# Power.net
KiCad netlist of a schematic drawn in Altium Designer
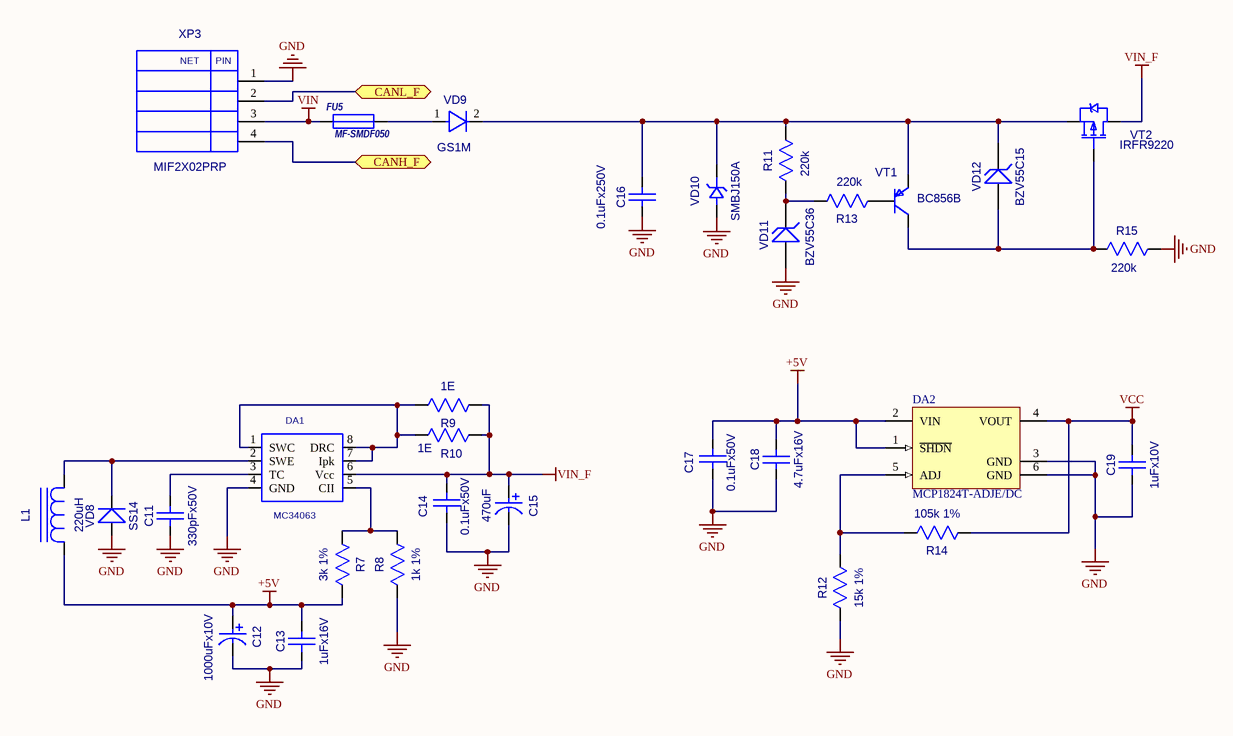
[diagram p0: Power.SchDoc]

(export (version "E")
  (design (tool "Eeschema 10.0.6"))
  (components
    (comp (ref "C11")
      (value "330pFx50V")
      (footprint "CC0603-3M")
      (description "CC0603")
      (libsource (lib "gprs_modem") (part "CC0603"))
    )
    (comp (ref "C12")
      (value "1000uFx10V")
      (footprint "CC8X3.5")
      (description "CAP0.35")
      (libsource (lib "gprs_modem") (part "CAP0.35"))
    )
    (comp (ref "C13")
      (value "1uFx16V")
      (footprint "CC0603-3M")
      (description "CC0603")
      (libsource (lib "gprs_modem") (part "CC0603"))
    )
    (comp (ref "C14")
      (value "0.1uFx50V")
      (footprint "CC0603-3M")
      (description "CC0603")
      (libsource (lib "gprs_modem") (part "CC0603"))
    )
    (comp (ref "C15")
      (value "470uF")
      (footprint "CC16X10_CAP0.5(1)(Primary)")
      (description "CAP0.5(1)")
      (libsource (lib "gprs_modem") (part "CAP0.5(1)"))
    )
    (comp (ref "C16")
      (value "0.1uFx250V")
      (footprint "CC1206-MIDI")
      (description "CC1206")
      (libsource (lib "gprs_modem") (part "CC1206"))
    )
    (comp (ref "C17")
      (value "0.1uFx50V")
      (footprint "CC0603-3M")
      (description "CC0603")
      (libsource (lib "gprs_modem") (part "CC0603"))
    )
    (comp (ref "C18")
      (value "4.7uFx16V")
      (footprint "CC0805-MIDI-2M1")
      (description "CC0805")
      (libsource (lib "gprs_modem") (part "CC0805"))
    )
    (comp (ref "C19")
      (value "1uFx10V")
      (footprint "CC0603-3M")
      (description "CC0603")
      (libsource (lib "gprs_modem") (part "CC0603"))
    )
    (comp (ref "DA1") (value "MC34063") (footprint "SO-8") (libsource (lib "Schetchik") (part "MC34063")))
    (comp (ref "DA2")
      (value "MCP1824T-ADJE/DC")
      (footprint "SOT223-6")
      (fields (field (name "PUBLISHER") "Altium Limited"))
      (libsource (lib "gprs_modem") (part "MCP1824T-ADJE/DC"))
    )
    (comp (ref "FU5")
      (value "MF-SMDF050")
      (footprint "MF-SMDF")
      (description "MF-SMDF")
      (libsource (lib "gprs_modem") (part "MF-SMDF"))
    )
    (comp (ref "L1")
      (value "220uH")
      (footprint "SDR0805")
      (description "SDR0805")
      (libsource (lib "gprs_modem") (part "SDR0805"))
    )
    (comp (ref "R7")
      (value "3k 1%")
      (footprint "RC0603-3M")
      (description "RC0603")
      (libsource (lib "gprs_modem") (part "RC0603"))
    )
    (comp (ref "R8")
      (value "1k 1%")
      (footprint "RC0603-3M")
      (description "RC0603")
      (libsource (lib "gprs_modem") (part "RC0603"))
    )
    (comp (ref "R9")
      (value "1E")
      (footprint "RC0805_IPC_NOM")
      (description "RC0805")
      (libsource (lib "gprs_modem") (part "RC0805"))
    )
    (comp (ref "R10")
      (value "1E")
      (footprint "RC0805_IPC_NOM")
      (description "RC0805")
      (libsource (lib "gprs_modem") (part "RC0805"))
    )
    (comp (ref "R11")
      (value "220k")
      (footprint "RC1206-2M")
      (description "RC1206")
      (libsource (lib "gprs_modem") (part "RC1206"))
    )
    (comp (ref "R12")
      (value "15k 1%")
      (footprint "RC0603-3M")
      (description "RC0603")
      (libsource (lib "gprs_modem") (part "RC0603"))
    )
    (comp (ref "R13")
      (value "220k")
      (footprint "RC1206-2M")
      (description "RC1206")
      (libsource (lib "gprs_modem") (part "RC1206"))
    )
    (comp (ref "R14")
      (value "105k 1%")
      (footprint "RC0603-3M")
      (description "RC0603")
      (libsource (lib "gprs_modem") (part "RC0603"))
    )
    (comp (ref "R15")
      (value "220k")
      (footprint "RC1206-2M")
      (description "RC1206")
      (libsource (lib "gprs_modem") (part "RC1206"))
    )
    (comp (ref "VD8")
      (value "SS14")
      (footprint "SMA")
      (description "Schottky Rectifier")
      (libsource (lib "gprs_modem") (part "SS14"))
    )
    (comp (ref "VD9") (value "GS1M") (footprint "SMA") (libsource (lib "Schetchik") (part "GS1M")))
    (comp (ref "VD10")
      (value "SMBJ150A")
      (footprint "SMB")
      (description "SMBJ")
      (libsource (lib "gprs_modem") (part "SMBJ"))
    )
    (comp (ref "VD11")
      (value "BZV55C36")
      (footprint "SOD-80")
      (description "Zener Voltage Regulator Diode")
      (libsource (lib "gprs_modem") (part "BZV55C12"))
    )
    (comp (ref "VD12")
      (value "BZV55C15")
      (footprint "SOD-80")
      (description "Zener Voltage Regulator Diode")
      (libsource (lib "gprs_modem") (part "BZV55C12"))
    )
    (comp (ref "VT1")
      (value "BC856B")
      (footprint "SOT-23(123)")
      (libsource (lib "Schetchik") (part "BC856B"))
    )
    (comp (ref "VT2")
      (value "IRFR9220")
      (footprint "D-PAK(TO-252AA)")
      (description "HEXFET Power MOSFET")
      (libsource (lib "gprs_modem") (part "IRFR9220"))
    )
    (comp (ref "XP3")
      (value "MIF2X02PRP")
      (footprint "MIF2X02PRP")
      (libsource (lib "Schetchik") (part "MIF2X02PRP"))
    )
  )
  (nets
    (net (code "1") (name "+5V") (class "Default")
      (node (ref "C12") (pin "1") (pintype "passive"))
      (node (ref "C13") (pin "2") (pinfunction "B_2") (pintype "passive"))
      (node (ref "C17") (pin "1") (pinfunction "A_1") (pintype "passive"))
      (node (ref "C18") (pin "2") (pinfunction "B_2") (pintype "passive"))
      (node (ref "DA2") (pin "1") (pinfunction "~{SHDN}_1") (pintype "input"))
      (node (ref "DA2") (pin "2") (pinfunction "VIN_2") (pintype "power_in"))
      (node (ref "L1") (pin "1") (pinfunction "C_1") (pintype "passive"))
      (node (ref "R7") (pin "2") (pinfunction "B_2") (pintype "passive"))
    )
    (net (code "2") (name "/CANH_F") (class "Default")
      (node (ref "XP3") (pin "4") (pinfunction "4_4") (pintype "passive"))
    )
    (net (code "3") (name "/CANL_F") (class "Default")
      (node (ref "XP3") (pin "2") (pinfunction "2_2") (pintype "passive"))
    )
    (net (code "4") (name "GND") (class "Default")
      (node (ref "C11") (pin "1") (pinfunction "A_1") (pintype "passive"))
      (node (ref "C12") (pin "2") (pintype "passive"))
      (node (ref "C13") (pin "1") (pinfunction "A_1") (pintype "passive"))
      (node (ref "C14") (pin "2") (pinfunction "B_2") (pintype "passive"))
      (node (ref "C15") (pin "1") (pintype "passive"))
      (node (ref "C16") (pin "1") (pinfunction "A_1") (pintype "passive"))
      (node (ref "C17") (pin "2") (pinfunction "B_2") (pintype "passive"))
      (node (ref "C18") (pin "1") (pinfunction "A_1") (pintype "passive"))
      (node (ref "C19") (pin "1") (pinfunction "A_1") (pintype "passive"))
      (node (ref "DA1") (pin "4") (pinfunction "GND_4") (pintype "passive"))
      (node (ref "DA2") (pin "3") (pinfunction "GND_3") (pintype "power_in"))
      (node (ref "DA2") (pin "6") (pinfunction "GND_6") (pintype "power_in"))
      (node (ref "R12") (pin "1") (pinfunction "A_1") (pintype "passive"))
      (node (ref "R15") (pin "2") (pinfunction "B_2") (pintype "passive"))
      (node (ref "R8") (pin "1") (pinfunction "A_1") (pintype "passive"))
      (node (ref "VD10") (pin "1") (pinfunction "A_1") (pintype "passive"))
      (node (ref "VD11") (pin "1") (pinfunction "A_1") (pintype "passive"))
      (node (ref "VD8") (pin "1") (pinfunction "A_1") (pintype "passive"))
      (node (ref "XP3") (pin "1") (pinfunction "1_1") (pintype "passive"))
    )
    (net (code "5") (name "Net-(C11-B)") (class "Default")
      (node (ref "C11") (pin "2") (pinfunction "B_2") (pintype "passive"))
      (node (ref "DA1") (pin "3") (pinfunction "TC_3") (pintype "passive"))
    )
    (net (code "6") (name "Net-(C16-B)") (class "Default")
      (node (ref "C16") (pin "2") (pinfunction "B_2") (pintype "passive"))
      (node (ref "R11") (pin "2") (pinfunction "B_2") (pintype "passive"))
      (node (ref "VD10") (pin "2") (pinfunction "K_2") (pintype "passive"))
      (node (ref "VD12") (pin "2") (pintype "passive"))
      (node (ref "VD9") (pin "2") (pinfunction "K_2") (pintype "passive"))
      (node (ref "VT1") (pin "2") (pinfunction "E_2") (pintype "passive"))
      (node (ref "VT2") (pin "2") (pinfunction "S_2") (pintype "passive"))
    )
    (net (code "7") (name "Net-(DA1-CII)") (class "Default")
      (node (ref "DA1") (pin "5") (pinfunction "CII_5") (pintype "passive"))
      (node (ref "R7") (pin "1") (pinfunction "A_1") (pintype "passive"))
      (node (ref "R8") (pin "2") (pinfunction "B_2") (pintype "passive"))
    )
    (net (code "8") (name "Net-(DA1-DRC)") (class "Default")
      (node (ref "DA1") (pin "1") (pinfunction "SWC_1") (pintype "passive"))
      (node (ref "DA1") (pin "7") (pinfunction "Ipk_7") (pintype "passive"))
      (node (ref "DA1") (pin "8") (pinfunction "DRC_8") (pintype "passive"))
      (node (ref "R10") (pin "2") (pinfunction "B_2") (pintype "passive"))
      (node (ref "R9") (pin "2") (pinfunction "B_2") (pintype "passive"))
    )
    (net (code "9") (name "Net-(DA1-SWE)") (class "Default")
      (node (ref "DA1") (pin "2") (pinfunction "SWE_2") (pintype "passive"))
      (node (ref "L1") (pin "2") (pinfunction "A_2") (pintype "passive"))
      (node (ref "VD8") (pin "2") (pinfunction "K_2") (pintype "passive"))
    )
    (net (code "10") (name "Net-(DA2-ADJ)") (class "Default")
      (node (ref "DA2") (pin "5") (pinfunction "ADJ_5") (pintype "input"))
      (node (ref "R12") (pin "2") (pinfunction "B_2") (pintype "passive"))
      (node (ref "R14") (pin "2") (pinfunction "B_2") (pintype "passive"))
    )
    (net (code "11") (name "Net-(R11-A)") (class "Default")
      (node (ref "R11") (pin "1") (pinfunction "A_1") (pintype "passive"))
      (node (ref "R13") (pin "2") (pinfunction "B_2") (pintype "passive"))
      (node (ref "VD11") (pin "2") (pintype "passive"))
    )
    (net (code "12") (name "Net-(R13-A)") (class "Default")
      (node (ref "R13") (pin "1") (pinfunction "A_1") (pintype "passive"))
      (node (ref "VT1") (pin "1") (pinfunction "B_1") (pintype "passive"))
    )
    (net (code "13") (name "Net-(R15-A)") (class "Default")
      (node (ref "R15") (pin "1") (pinfunction "A_1") (pintype "passive"))
      (node (ref "VD12") (pin "1") (pinfunction "A_1") (pintype "passive"))
      (node (ref "VT1") (pin "3") (pinfunction "C_3") (pintype "passive"))
      (node (ref "VT2") (pin "1") (pinfunction "G_1") (pintype "passive"))
    )
    (net (code "14") (name "Net-(VD9-A)") (class "Default")
      (node (ref "FU5") (pin "2") (pintype "passive"))
      (node (ref "VD9") (pin "1") (pinfunction "A_1") (pintype "passive"))
    )
    (net (code "15") (name "VCC") (class "Default")
      (node (ref "C19") (pin "2") (pinfunction "B_2") (pintype "passive"))
      (node (ref "DA2") (pin "4") (pinfunction "VOUT_4") (pintype "power_in"))
      (node (ref "R14") (pin "1") (pinfunction "A_1") (pintype "passive"))
    )
    (net (code "16") (name "VIN") (class "Default")
      (node (ref "FU5") (pin "1") (pintype "passive"))
      (node (ref "XP3") (pin "3") (pinfunction "3_3") (pintype "passive"))
    )
    (net (code "17") (name "VIN_F") (class "Default")
      (node (ref "C14") (pin "1") (pinfunction "A_1") (pintype "passive"))
      (node (ref "C15") (pin "2") (pintype "passive"))
      (node (ref "DA1") (pin "6") (pinfunction "Vcc_6") (pintype "passive"))
      (node (ref "R10") (pin "1") (pinfunction "A_1") (pintype "passive"))
      (node (ref "R9") (pin "1") (pinfunction "A_1") (pintype "passive"))
      (node (ref "VT2") (pin "3") (pinfunction "D_3") (pintype "passive"))
    )
  )
)
